# ECL_Fanout_X3.net
KiCad netlist of a schematic drawn in Altium Designer
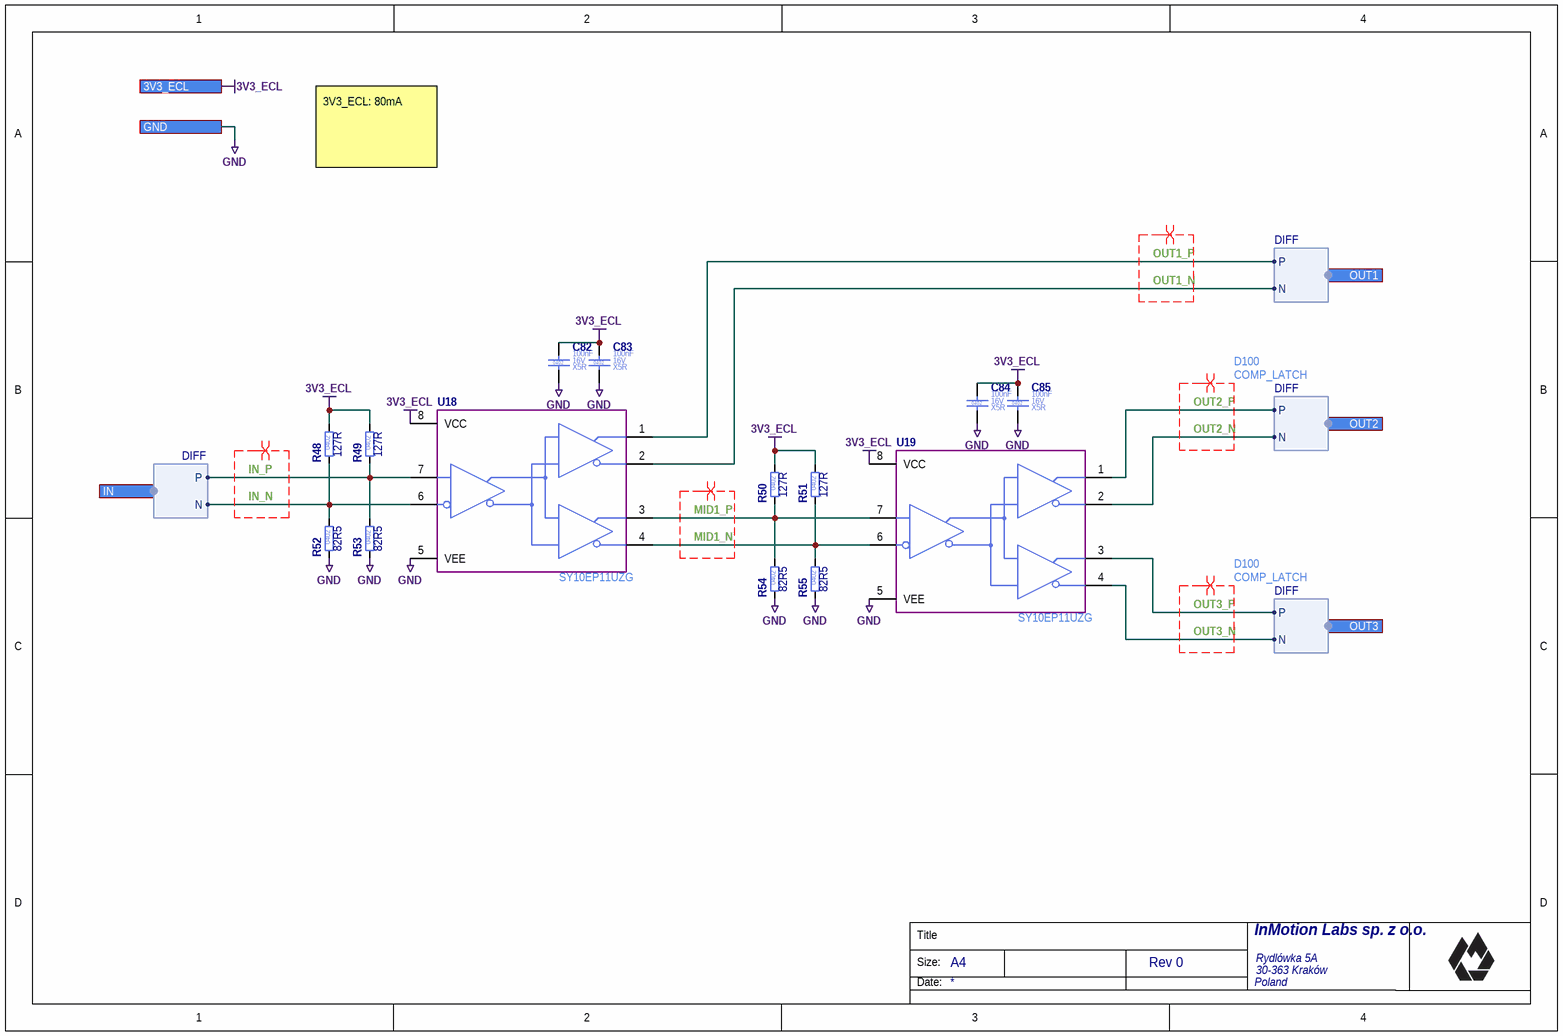
[diagram p0: ECL_Fanout_X3.SchDoc]

(export (version "E")
  (design (tool "Eeschema 10.0.6"))
  (components
    (comp (ref "C82")
      (value "C_100NF_16V_X5R_0402_10")
      (footprint "C_0402_1005")
      (description "Ceramic Capacitor")
      (fields
        (field (name "CASE/PACKAGE") "0402")
        (field (name "VOLTAGE RATING (DC)") "16V")
        (field (name "DIELECTRIC") "X5R")
        (field (name "CAPACITANCE") "100nF")
        (field (name "TOLERANCE") "10%")
        (field (name "MANUFACTURER PART NUMBER") "EMK105BJ104KV-F")
      )
      (libsource (lib "7Sigma") (part "C"))
    )
    (comp (ref "C83")
      (value "C_100NF_16V_X5R_0402_10")
      (footprint "C_0402_1005")
      (description "Ceramic Capacitor")
      (fields
        (field (name "CASE/PACKAGE") "0402")
        (field (name "VOLTAGE RATING (DC)") "16V")
        (field (name "DIELECTRIC") "X5R")
        (field (name "CAPACITANCE") "100nF")
        (field (name "TOLERANCE") "10%")
        (field (name "MANUFACTURER PART NUMBER") "EMK105BJ104KV-F")
      )
      (libsource (lib "7Sigma") (part "C"))
    )
    (comp (ref "C84")
      (value "C_100NF_16V_X5R_0402_10")
      (footprint "C_0402_1005")
      (description "Ceramic Capacitor")
      (fields
        (field (name "CASE/PACKAGE") "0402")
        (field (name "VOLTAGE RATING (DC)") "16V")
        (field (name "DIELECTRIC") "X5R")
        (field (name "CAPACITANCE") "100nF")
        (field (name "TOLERANCE") "10%")
        (field (name "MANUFACTURER PART NUMBER") "EMK105BJ104KV-F")
      )
      (libsource (lib "7Sigma") (part "C"))
    )
    (comp (ref "C85")
      (value "C_100NF_16V_X5R_0402_10")
      (footprint "C_0402_1005")
      (description "Ceramic Capacitor")
      (fields
        (field (name "CASE/PACKAGE") "0402")
        (field (name "VOLTAGE RATING (DC)") "16V")
        (field (name "DIELECTRIC") "X5R")
        (field (name "CAPACITANCE") "100nF")
        (field (name "TOLERANCE") "10%")
        (field (name "MANUFACTURER PART NUMBER") "EMK105BJ104KV-F")
      )
      (libsource (lib "7Sigma") (part "C"))
    )
    (comp (ref "R48")
      (value "R_127R_0402_1")
      (footprint "R_0402_1005")
      (description "Thick Film Resistor")
      (fields
        (field (name "RESISTANCE") "127R")
        (field (name "CASE/PACKAGE") "0402")
        (field (name "TOLERANCE") "1%")
        (field (name "MANUFACTURER") "Yageo")
      )
      (libsource (lib "7Sigma") (part "R"))
    )
    (comp (ref "R49")
      (value "R_127R_0402_1")
      (footprint "R_0402_1005")
      (description "Thick Film Resistor")
      (fields
        (field (name "RESISTANCE") "127R")
        (field (name "CASE/PACKAGE") "0402")
        (field (name "TOLERANCE") "1%")
        (field (name "MANUFACTURER") "Yageo")
      )
      (libsource (lib "7Sigma") (part "R"))
    )
    (comp (ref "R50")
      (value "R_127R_0402_1")
      (footprint "R_0402_1005")
      (description "Thick Film Resistor")
      (fields
        (field (name "RESISTANCE") "127R")
        (field (name "CASE/PACKAGE") "0402")
        (field (name "TOLERANCE") "1%")
        (field (name "MANUFACTURER") "Yageo")
      )
      (libsource (lib "7Sigma") (part "R"))
    )
    (comp (ref "R51")
      (value "R_127R_0402_1")
      (footprint "R_0402_1005")
      (description "Thick Film Resistor")
      (fields
        (field (name "RESISTANCE") "127R")
        (field (name "CASE/PACKAGE") "0402")
        (field (name "TOLERANCE") "1%")
        (field (name "MANUFACTURER") "Yageo")
      )
      (libsource (lib "7Sigma") (part "R"))
    )
    (comp (ref "R52")
      (value "R_82R5_0402_1")
      (footprint "R_0402_1005")
      (description "Thick Film Resistor")
      (fields
        (field (name "RESISTANCE") "82R5")
        (field (name "CASE/PACKAGE") "0402")
        (field (name "TOLERANCE") "1%")
        (field (name "MANUFACTURER") "Yageo")
      )
      (libsource (lib "7Sigma") (part "R"))
    )
    (comp (ref "R53")
      (value "R_82R5_0402_1")
      (footprint "R_0402_1005")
      (description "Thick Film Resistor")
      (fields
        (field (name "RESISTANCE") "82R5")
        (field (name "CASE/PACKAGE") "0402")
        (field (name "TOLERANCE") "1%")
        (field (name "MANUFACTURER") "Yageo")
      )
      (libsource (lib "7Sigma") (part "R"))
    )
    (comp (ref "R54")
      (value "R_82R5_0402_1")
      (footprint "R_0402_1005")
      (description "Thick Film Resistor")
      (fields
        (field (name "RESISTANCE") "82R5")
        (field (name "CASE/PACKAGE") "0402")
        (field (name "TOLERANCE") "1%")
        (field (name "MANUFACTURER") "Yageo")
      )
      (libsource (lib "7Sigma") (part "R"))
    )
    (comp (ref "R55")
      (value "R_82R5_0402_1")
      (footprint "R_0402_1005")
      (description "Thick Film Resistor")
      (fields
        (field (name "RESISTANCE") "82R5")
        (field (name "CASE/PACKAGE") "0402")
        (field (name "TOLERANCE") "1%")
        (field (name "MANUFACTURER") "Yageo")
      )
      (libsource (lib "7Sigma") (part "R"))
    )
    (comp (ref "U18")
      (value "SY10EP11UZG")
      (footprint "SOIC127P600X170-8N")
      (description "1:2 PECL Fanout Buffer")
      (fields
        (field (name "MANUFACTURER") "Microchip")
        (field (name "MANUFACTURER PART NUMBER") "SY10EP11UZG")
      )
      (libsource (lib "7Sigma") (part "SY10EP11U"))
    )
    (comp (ref "U19")
      (value "SY10EP11UZG")
      (footprint "SOIC127P600X170-8N")
      (description "1:2 PECL Fanout Buffer")
      (fields
        (field (name "MANUFACTURER") "Microchip")
        (field (name "MANUFACTURER PART NUMBER") "SY10EP11UZG")
      )
      (libsource (lib "7Sigma") (part "SY10EP11U"))
    )
  )
  (nets
    (net (code "2") (name "/IN_N") (class "Default")
      (node (ref "R48") (pin "1") (pinfunction "1_1") (pintype "passive"))
      (node (ref "R52") (pin "2") (pinfunction "2_2") (pintype "passive"))
      (node (ref "U18") (pin "6") (pinfunction "D_6") (pintype "passive"))
    )
    (net (code "3") (name "/IN_P") (class "Default")
      (node (ref "R49") (pin "1") (pinfunction "1_1") (pintype "passive"))
      (node (ref "R53") (pin "2") (pinfunction "2_2") (pintype "passive"))
      (node (ref "U18") (pin "7") (pinfunction "D_7") (pintype "passive"))
    )
    (net (code "4") (name "/MID1_N") (class "Default")
      (node (ref "R51") (pin "1") (pinfunction "1_1") (pintype "passive"))
      (node (ref "R55") (pin "2") (pinfunction "2_2") (pintype "passive"))
      (node (ref "U18") (pin "4") (pinfunction "Q1_4") (pintype "passive"))
      (node (ref "U19") (pin "6") (pinfunction "D_6") (pintype "passive"))
    )
    (net (code "5") (name "/MID1_P") (class "Default")
      (node (ref "R50") (pin "1") (pinfunction "1_1") (pintype "passive"))
      (node (ref "R54") (pin "2") (pinfunction "2_2") (pintype "passive"))
      (node (ref "U18") (pin "3") (pinfunction "Q1_3") (pintype "passive"))
      (node (ref "U19") (pin "7") (pinfunction "D_7") (pintype "passive"))
    )
    (net (code "6") (name "/OUT1_N") (class "Default")
      (node (ref "U18") (pin "2") (pinfunction "/Q0_2") (pintype "passive"))
    )
    (net (code "7") (name "/OUT1_P") (class "Default")
      (node (ref "U18") (pin "1") (pinfunction "Q0_1") (pintype "passive"))
    )
    (net (code "8") (name "/OUT2_N") (class "Default")
      (node (ref "U19") (pin "2") (pinfunction "/Q0_2") (pintype "passive"))
    )
    (net (code "9") (name "/OUT2_P") (class "Default")
      (node (ref "U19") (pin "1") (pinfunction "Q0_1") (pintype "passive"))
    )
    (net (code "10") (name "/OUT3_N") (class "Default")
      (node (ref "U19") (pin "4") (pinfunction "Q1_4") (pintype "passive"))
    )
    (net (code "11") (name "/OUT3_P") (class "Default")
      (node (ref "U19") (pin "3") (pinfunction "Q1_3") (pintype "passive"))
    )
    (net (code "13") (name "3V3_ECL") (class "Default")
      (node (ref "C82") (pin "1") (pinfunction "1_1") (pintype "passive"))
      (node (ref "C83") (pin "1") (pinfunction "1_1") (pintype "passive"))
      (node (ref "C84") (pin "1") (pinfunction "1_1") (pintype "passive"))
      (node (ref "C85") (pin "1") (pinfunction "1_1") (pintype "passive"))
      (node (ref "R48") (pin "2") (pinfunction "2_2") (pintype "passive"))
      (node (ref "R49") (pin "2") (pinfunction "2_2") (pintype "passive"))
      (node (ref "R50") (pin "2") (pinfunction "2_2") (pintype "passive"))
      (node (ref "R51") (pin "2") (pinfunction "2_2") (pintype "passive"))
      (node (ref "U18") (pin "8") (pinfunction "VCC_8") (pintype "passive"))
      (node (ref "U19") (pin "8") (pinfunction "VCC_8") (pintype "passive"))
    )
    (net (code "14") (name "GND") (class "Default")
      (node (ref "C82") (pin "2") (pinfunction "2_2") (pintype "passive"))
      (node (ref "C83") (pin "2") (pinfunction "2_2") (pintype "passive"))
      (node (ref "C84") (pin "2") (pinfunction "2_2") (pintype "passive"))
      (node (ref "C85") (pin "2") (pinfunction "2_2") (pintype "passive"))
      (node (ref "R52") (pin "1") (pinfunction "1_1") (pintype "passive"))
      (node (ref "R53") (pin "1") (pinfunction "1_1") (pintype "passive"))
      (node (ref "R54") (pin "1") (pinfunction "1_1") (pintype "passive"))
      (node (ref "R55") (pin "1") (pinfunction "1_1") (pintype "passive"))
      (node (ref "U18") (pin "5") (pinfunction "VEE_5") (pintype "passive"))
      (node (ref "U19") (pin "5") (pinfunction "VEE_5") (pintype "passive"))
    )
  )
)
